# view-board-mid.net
KiCad netlist of a schematic drawn in EAGLE
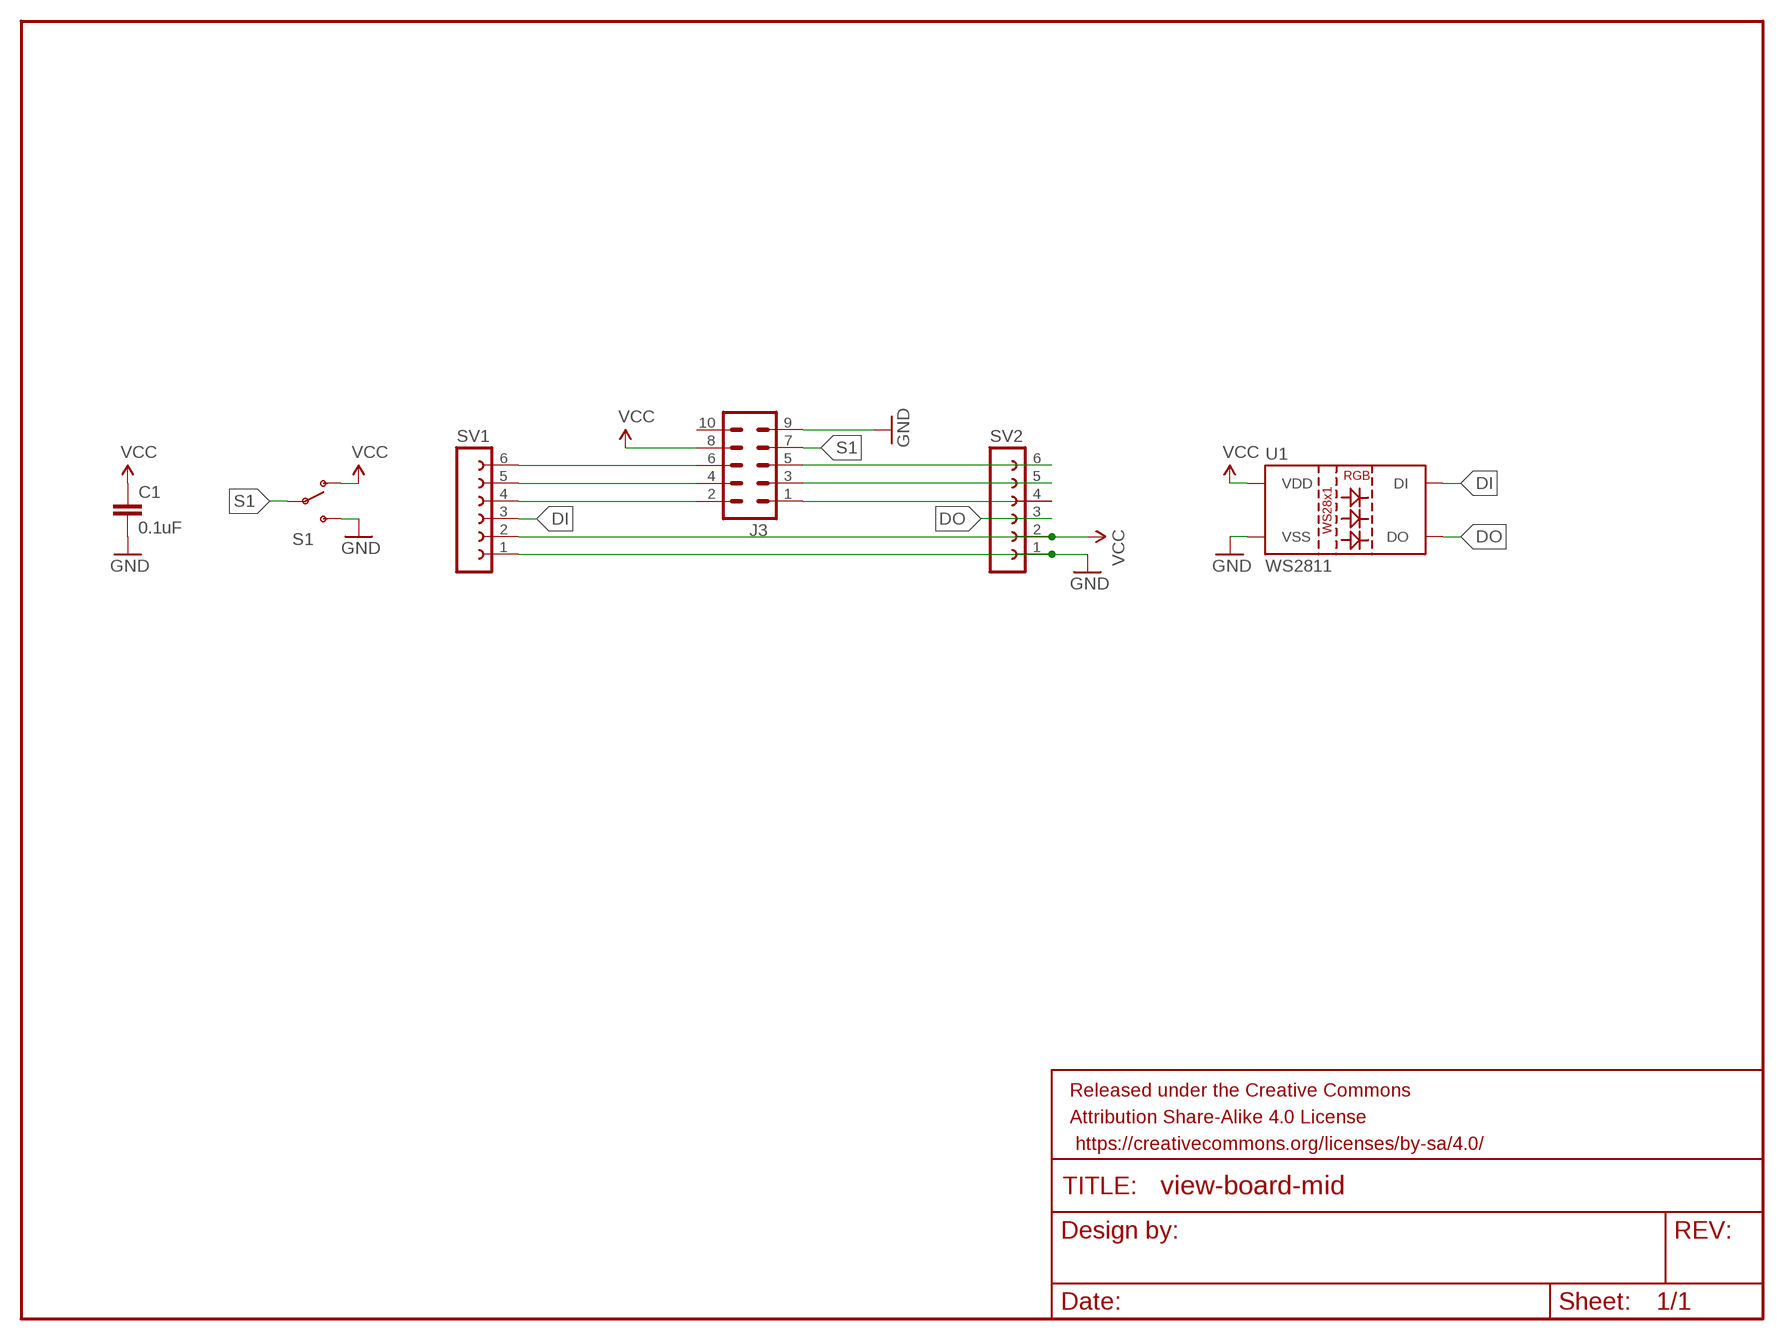
[diagram p0: schematic, sheet 1]

(export (version "E")
  (design (tool "Eeschema 10.0.6"))
  (components
    (comp (ref "C1")
      (value "0.1uF")
      (footprint "eagle-import:0805")
      (libsource (lib "eagle-import") (part "CAP0805"))
    )
    (comp (ref "FRAME1")
      (value "FRAME-LETTER")
      (footprint "eagle-import:CREATIVE_COMMONS")
      (libsource (lib "eagle-import") (part "FRAME-LETTER"))
    )
    (comp (ref "J3")
      (value "M05X2SHD")
      (footprint "eagle-import:2X5-SHROUDED")
      (libsource (lib "eagle-import") (part "M05X2SHD"))
    )
    (comp (ref "S1")
      (value "SWITCH-SPDTPTH")
      (footprint "eagle-import:SWITCH-SPDT")
      (libsource (lib "eagle-import") (part "SWITCH-SPDTPTH"))
    )
    (comp (ref "SV1")
      (value "FE06-1")
      (footprint "eagle-import:FE06")
      (libsource (lib "eagle-import") (part "FE06-1"))
    )
    (comp (ref "SV2")
      (value "FE06-1")
      (footprint "eagle-import:FE06")
      (libsource (lib "eagle-import") (part "FE06-1"))
    )
    (comp (ref "U1")
      (value "WS2811")
      (footprint "eagle-import:LED-TRICOLOR-5050-IC")
      (libsource (lib "eagle-import") (part "LED-TRICOLOR-5050-ICWS2811"))
    )
  )
  (nets
    (net (code "1") (name "DI") (class "Default")
      (node (ref "SV1") (pin "3") (pinfunction "3_3") (pintype "passive"))
      (node (ref "U1") (pin "2") (pinfunction "DI_2") (pintype "bidirectional"))
    )
    (net (code "2") (name "DO") (class "Default")
      (node (ref "SV2") (pin "3") (pinfunction "3_3") (pintype "passive"))
      (node (ref "U1") (pin "1") (pinfunction "DO_1") (pintype "bidirectional"))
    )
    (net (code "3") (name "GND") (class "Default")
      (node (ref "C1") (pin "2") (pinfunction "2_2") (pintype "passive"))
      (node (ref "J3") (pin "9") (pinfunction "9_9") (pintype "passive"))
      (node (ref "S1") (pin "3") (pinfunction "S_3") (pintype "passive"))
      (node (ref "SV1") (pin "1") (pinfunction "1_1") (pintype "passive"))
      (node (ref "SV2") (pin "1") (pinfunction "1_1") (pintype "passive"))
      (node (ref "U1") (pin "6") (pinfunction "VSS_6") (pintype "bidirectional"))
    )
    (net (code "4") (name "Net-(J3-Pad1)") (class "Default")
      (node (ref "J3") (pin "1") (pinfunction "1_1") (pintype "passive"))
      (node (ref "SV2") (pin "4") (pinfunction "4_4") (pintype "passive"))
    )
    (net (code "5") (name "Net-(J3-Pad2)") (class "Default")
      (node (ref "J3") (pin "2") (pinfunction "2_2") (pintype "passive"))
      (node (ref "SV1") (pin "4") (pinfunction "4_4") (pintype "passive"))
    )
    (net (code "6") (name "Net-(J3-Pad3)") (class "Default")
      (node (ref "J3") (pin "3") (pinfunction "3_3") (pintype "passive"))
      (node (ref "SV2") (pin "5") (pinfunction "5_5") (pintype "passive"))
    )
    (net (code "7") (name "Net-(J3-Pad4)") (class "Default")
      (node (ref "J3") (pin "4") (pinfunction "4_4") (pintype "passive"))
      (node (ref "SV1") (pin "5") (pinfunction "5_5") (pintype "passive"))
    )
    (net (code "8") (name "Net-(J3-Pad5)") (class "Default")
      (node (ref "J3") (pin "5") (pinfunction "5_5") (pintype "passive"))
      (node (ref "SV2") (pin "6") (pinfunction "6_6") (pintype "passive"))
    )
    (net (code "9") (name "Net-(J3-Pad6)") (class "Default")
      (node (ref "J3") (pin "6") (pinfunction "6_6") (pintype "passive"))
      (node (ref "SV1") (pin "6") (pinfunction "6_6") (pintype "passive"))
    )
    (net (code "10") (name "S1") (class "Default")
      (node (ref "J3") (pin "7") (pinfunction "7_7") (pintype "passive"))
      (node (ref "S1") (pin "2") (pinfunction "P_2") (pintype "passive"))
    )
    (net (code "11") (name "VCC") (class "Default")
      (node (ref "C1") (pin "1") (pinfunction "1_1") (pintype "passive"))
      (node (ref "J3") (pin "8") (pinfunction "8_8") (pintype "passive"))
      (node (ref "S1") (pin "1") (pinfunction "O_1") (pintype "passive"))
      (node (ref "SV1") (pin "2") (pinfunction "2_2") (pintype "passive"))
      (node (ref "SV2") (pin "2") (pinfunction "2_2") (pintype "passive"))
      (node (ref "U1") (pin "3") (pinfunction "VDD_3") (pintype "bidirectional"))
      (node (ref "U1") (pin "5") (pinfunction "VDD_5") (pintype "bidirectional"))
    )
    (net (code "12") (name "unconnected-(J3-Pad10)") (class "Default")
      (node (ref "J3") (pin "10") (pinfunction "10_10") (pintype "passive"))
    )
  )
)
